# drawdio_v2.net
KiCad netlist of a schematic drawn in EAGLE
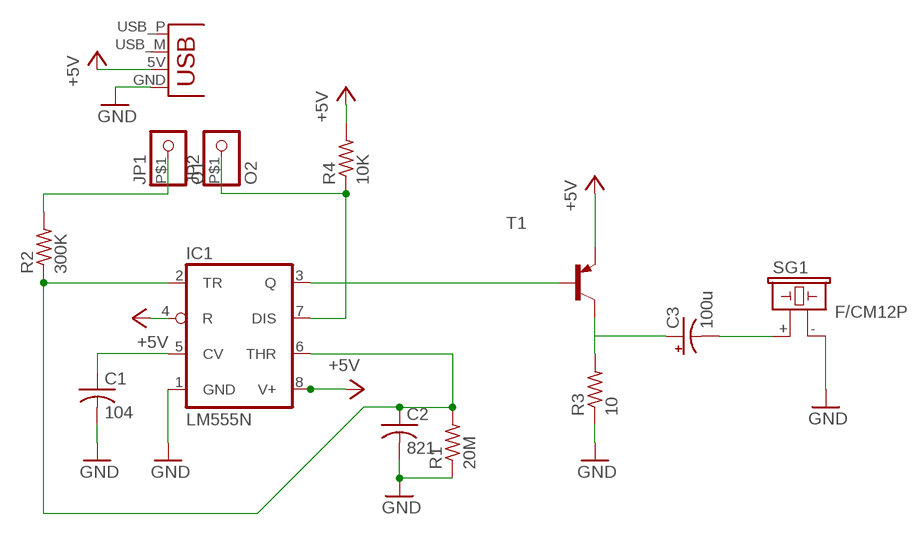
[diagram p0: schematic, sheet 1]

(export (version "E")
  (design (tool "Eeschema 10.0.6"))
  (components
    (comp (ref "C1")
      (value "104")
      (footprint "eagle-import:C025-030X050")
      (libsource (lib "eagle-import") (part "C-US025-030X050"))
    )
    (comp (ref "C2")
      (value "821")
      (footprint "eagle-import:C050-024X044")
      (libsource (lib "eagle-import") (part "C-US050-024X044"))
    )
    (comp (ref "C3")
      (value "100u")
      (footprint "eagle-import:E2,5-6E")
      (libsource (lib "eagle-import") (part "CPOL-USE2,5-6E"))
    )
    (comp (ref "IC1")
      (value "LM555N")
      (footprint "eagle-import:DIL08")
      (libsource (lib "eagle-import") (part "555NLM"))
    )
    (comp (ref "JP1")
      (value "O1")
      (footprint "eagle-import:1X1-BIGPOGO")
      (libsource (lib "eagle-import") (part "PINHD-1X1-BIGPOGO"))
    )
    (comp (ref "JP2")
      (value "O2")
      (footprint "eagle-import:1X1-BIGPOGO")
      (libsource (lib "eagle-import") (part "PINHD-1X1-BIGPOGO"))
    )
    (comp (ref "R1")
      (value "20M")
      (footprint "eagle-import:0207_7")
      (libsource (lib "eagle-import") (part "R-US_0207/7"))
    )
    (comp (ref "R2")
      (value "300K")
      (footprint "eagle-import:0207_7")
      (libsource (lib "eagle-import") (part "R-US_0207/7"))
    )
    (comp (ref "R3")
      (value "10")
      (footprint "eagle-import:0207_7")
      (libsource (lib "eagle-import") (part "R-US_0207/7"))
    )
    (comp (ref "R4")
      (value "10K")
      (footprint "eagle-import:0207_7")
      (libsource (lib "eagle-import") (part "R-US_0207/7"))
    )
    (comp (ref "SG1")
      (value "F/CM12P")
      (footprint "eagle-import:F_CM12P")
      (libsource (lib "eagle-import") (part "F/CM12P"))
    )
    (comp (ref "T1")
      (value "MPS2907A-PNP-TO92-CBE")
      (footprint "eagle-import:TO92-CBE")
      (libsource (lib "eagle-import") (part "-PNP-TO92-CBEMPS2907A"))
    )
    (comp (ref "X1")
      (value "USBPCB")
      (footprint "eagle-import:USB-A-PCB")
      (libsource (lib "eagle-import") (part "USBPCB"))
    )
  )
  (nets
    (net (code "1") (name "+5V") (class "Default")
      (node (ref "IC1") (pin "4") (pinfunction "R_4") (pintype "input"))
      (node (ref "IC1") (pin "8") (pinfunction "V+_8") (pintype "power_in"))
      (node (ref "R4") (pin "2") (pinfunction "2_2") (pintype "passive"))
      (node (ref "T1") (pin "E") (pinfunction "E_E") (pintype "passive"))
      (node (ref "X1") (pin "5V") (pinfunction "VBUS_5V") (pintype "bidirectional"))
    )
    (net (code "2") (name "GND") (class "Default")
      (node (ref "C1") (pin "2") (pinfunction "2_2") (pintype "passive"))
      (node (ref "C2") (pin "2") (pinfunction "2_2") (pintype "passive"))
      (node (ref "IC1") (pin "1") (pinfunction "GND_1") (pintype "power_in"))
      (node (ref "R1") (pin "1") (pinfunction "1_1") (pintype "passive"))
      (node (ref "R3") (pin "1") (pinfunction "1_1") (pintype "passive"))
      (node (ref "SG1") (pin "-") (pinfunction "2_-") (pintype "passive"))
      (node (ref "X1") (pin "GND") (pinfunction "GND_GND") (pintype "bidirectional"))
    )
    (net (code "3") (name "Net-(C3-Pad+)") (class "Default")
      (node (ref "C3") (pin "+") (pinfunction "+_+") (pintype "passive"))
      (node (ref "R3") (pin "2") (pinfunction "2_2") (pintype "passive"))
      (node (ref "T1") (pin "C") (pinfunction "C_C") (pintype "passive"))
    )
    (net (code "4") (name "Net-(IC1-CV)") (class "Default")
      (node (ref "C1") (pin "1") (pinfunction "1_1") (pintype "passive"))
      (node (ref "IC1") (pin "5") (pinfunction "CV_5") (pintype "input"))
    )
    (net (code "5") (name "Net-(IC1-DIS)") (class "Default")
      (node (ref "IC1") (pin "7") (pinfunction "DIS_7") (pintype "input"))
      (node (ref "JP2") (pin "P$1") (pinfunction "1_P$1") (pintype "passive"))
      (node (ref "R4") (pin "1") (pinfunction "1_1") (pintype "passive"))
    )
    (net (code "6") (name "Net-(IC1-Q)") (class "Default")
      (node (ref "IC1") (pin "3") (pinfunction "Q_3") (pintype "output"))
      (node (ref "T1") (pin "B") (pinfunction "B_B") (pintype "passive"))
    )
    (net (code "7") (name "Net-(IC1-THR)") (class "Default")
      (node (ref "C2") (pin "1") (pinfunction "1_1") (pintype "passive"))
      (node (ref "IC1") (pin "2") (pinfunction "TR_2") (pintype "input"))
      (node (ref "IC1") (pin "6") (pinfunction "THR_6") (pintype "input"))
      (node (ref "R1") (pin "2") (pinfunction "2_2") (pintype "passive"))
      (node (ref "R2") (pin "1") (pinfunction "1_1") (pintype "passive"))
    )
    (net (code "8") (name "Net-(JP1-1)") (class "Default")
      (node (ref "JP1") (pin "P$1") (pinfunction "1_P$1") (pintype "passive"))
      (node (ref "R2") (pin "2") (pinfunction "2_2") (pintype "passive"))
    )
    (net (code "9") (name "Net-(SG1-1)") (class "Default")
      (node (ref "C3") (pin "-") (pinfunction "-_-") (pintype "passive"))
      (node (ref "SG1") (pin "+") (pinfunction "1_+") (pintype "passive"))
    )
    (net (code "10") (name "unconnected-(X1-D+-PadUSB_P)") (class "Default")
      (node (ref "X1") (pin "USB_P") (pinfunction "D+_USB_P") (pintype "bidirectional"))
    )
    (net (code "11") (name "unconnected-(X1-D--PadUSB_M)") (class "Default")
      (node (ref "X1") (pin "USB_M") (pinfunction "D-_USB_M") (pintype "bidirectional"))
    )
  )
)
